# M8341X.net
KiCad netlist of a schematic drawn in EAGLE
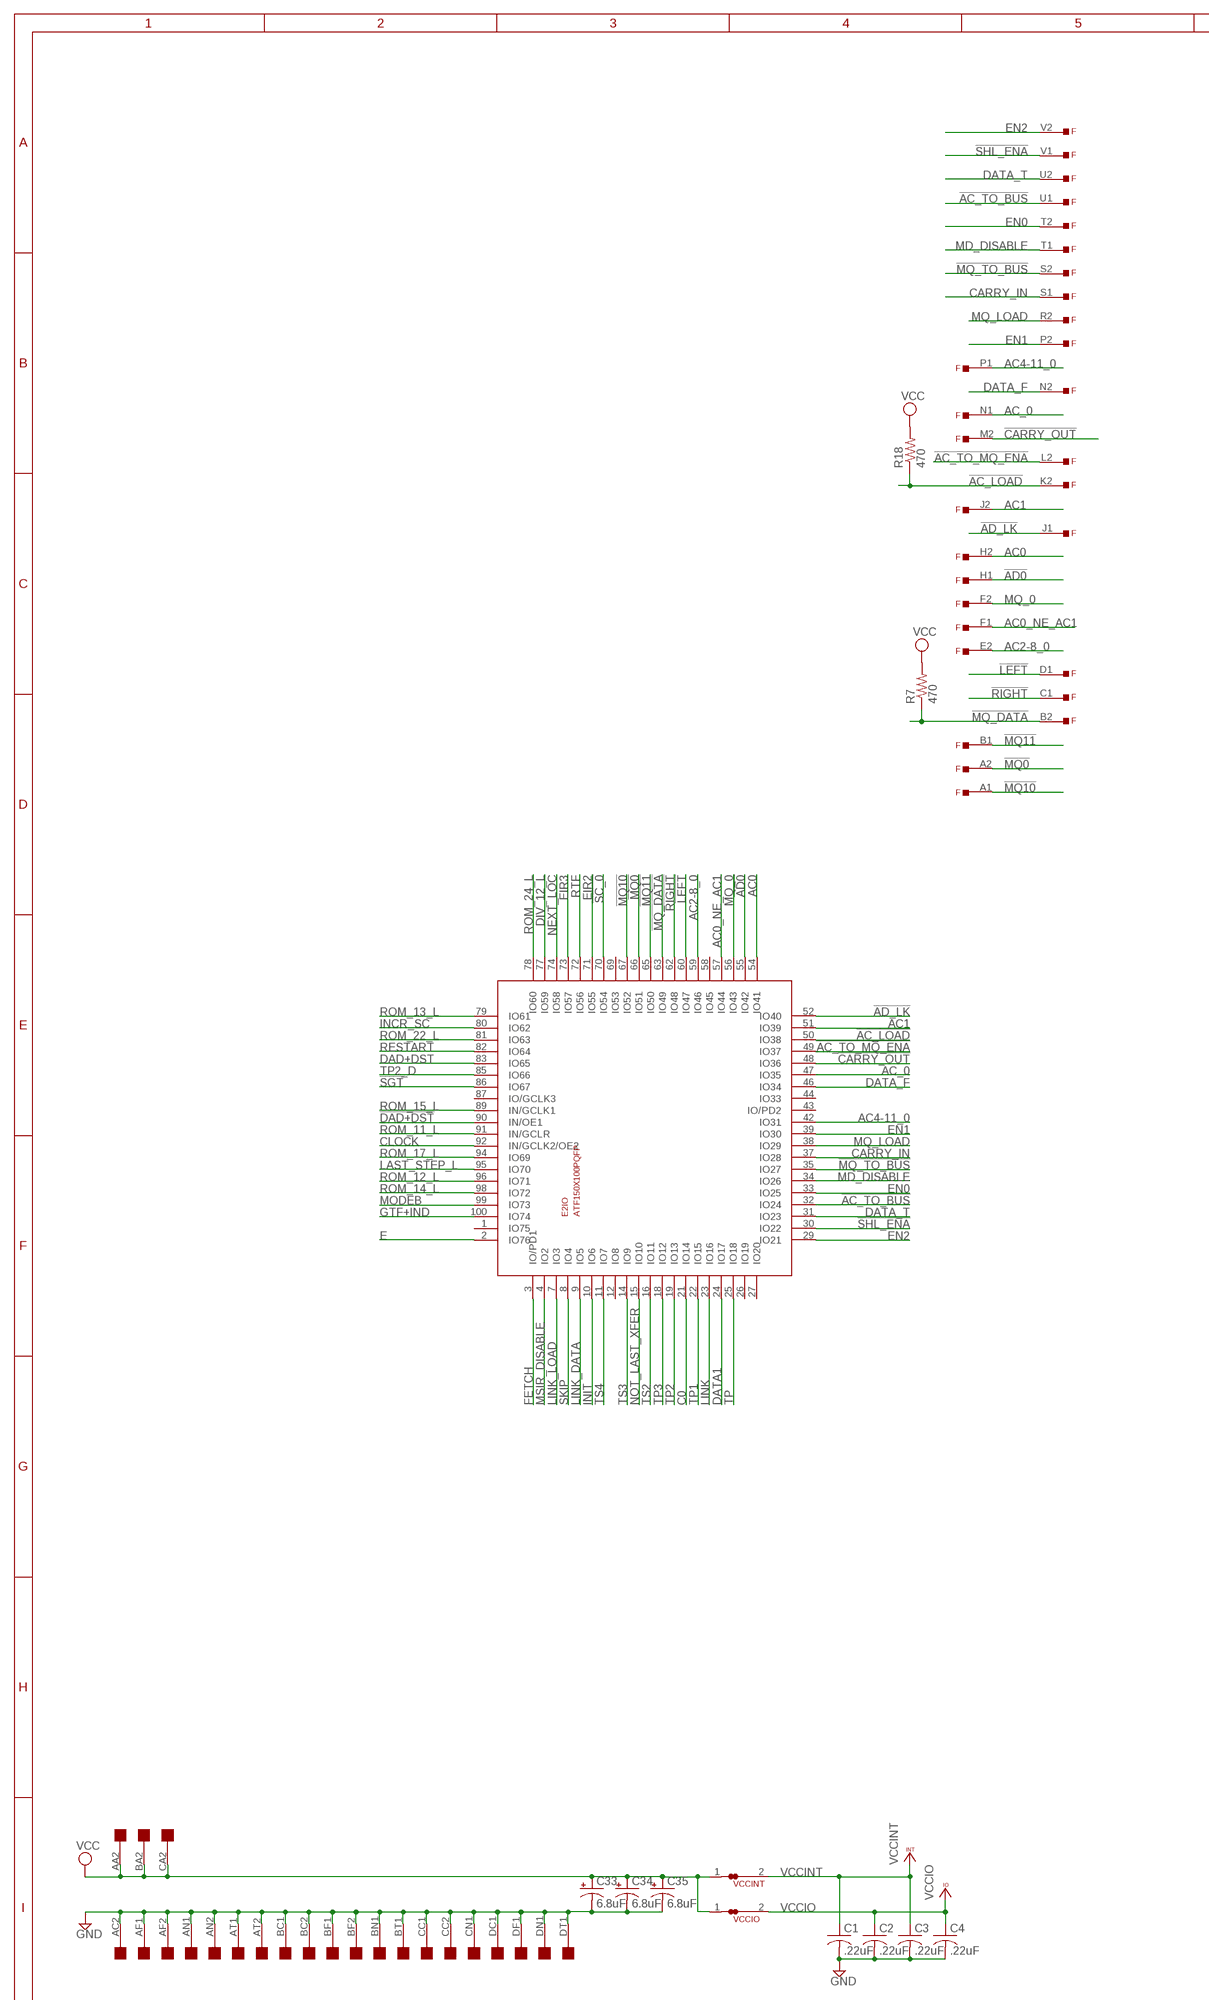
[diagram p0: schematic, sheet 1, part 1 of 2]
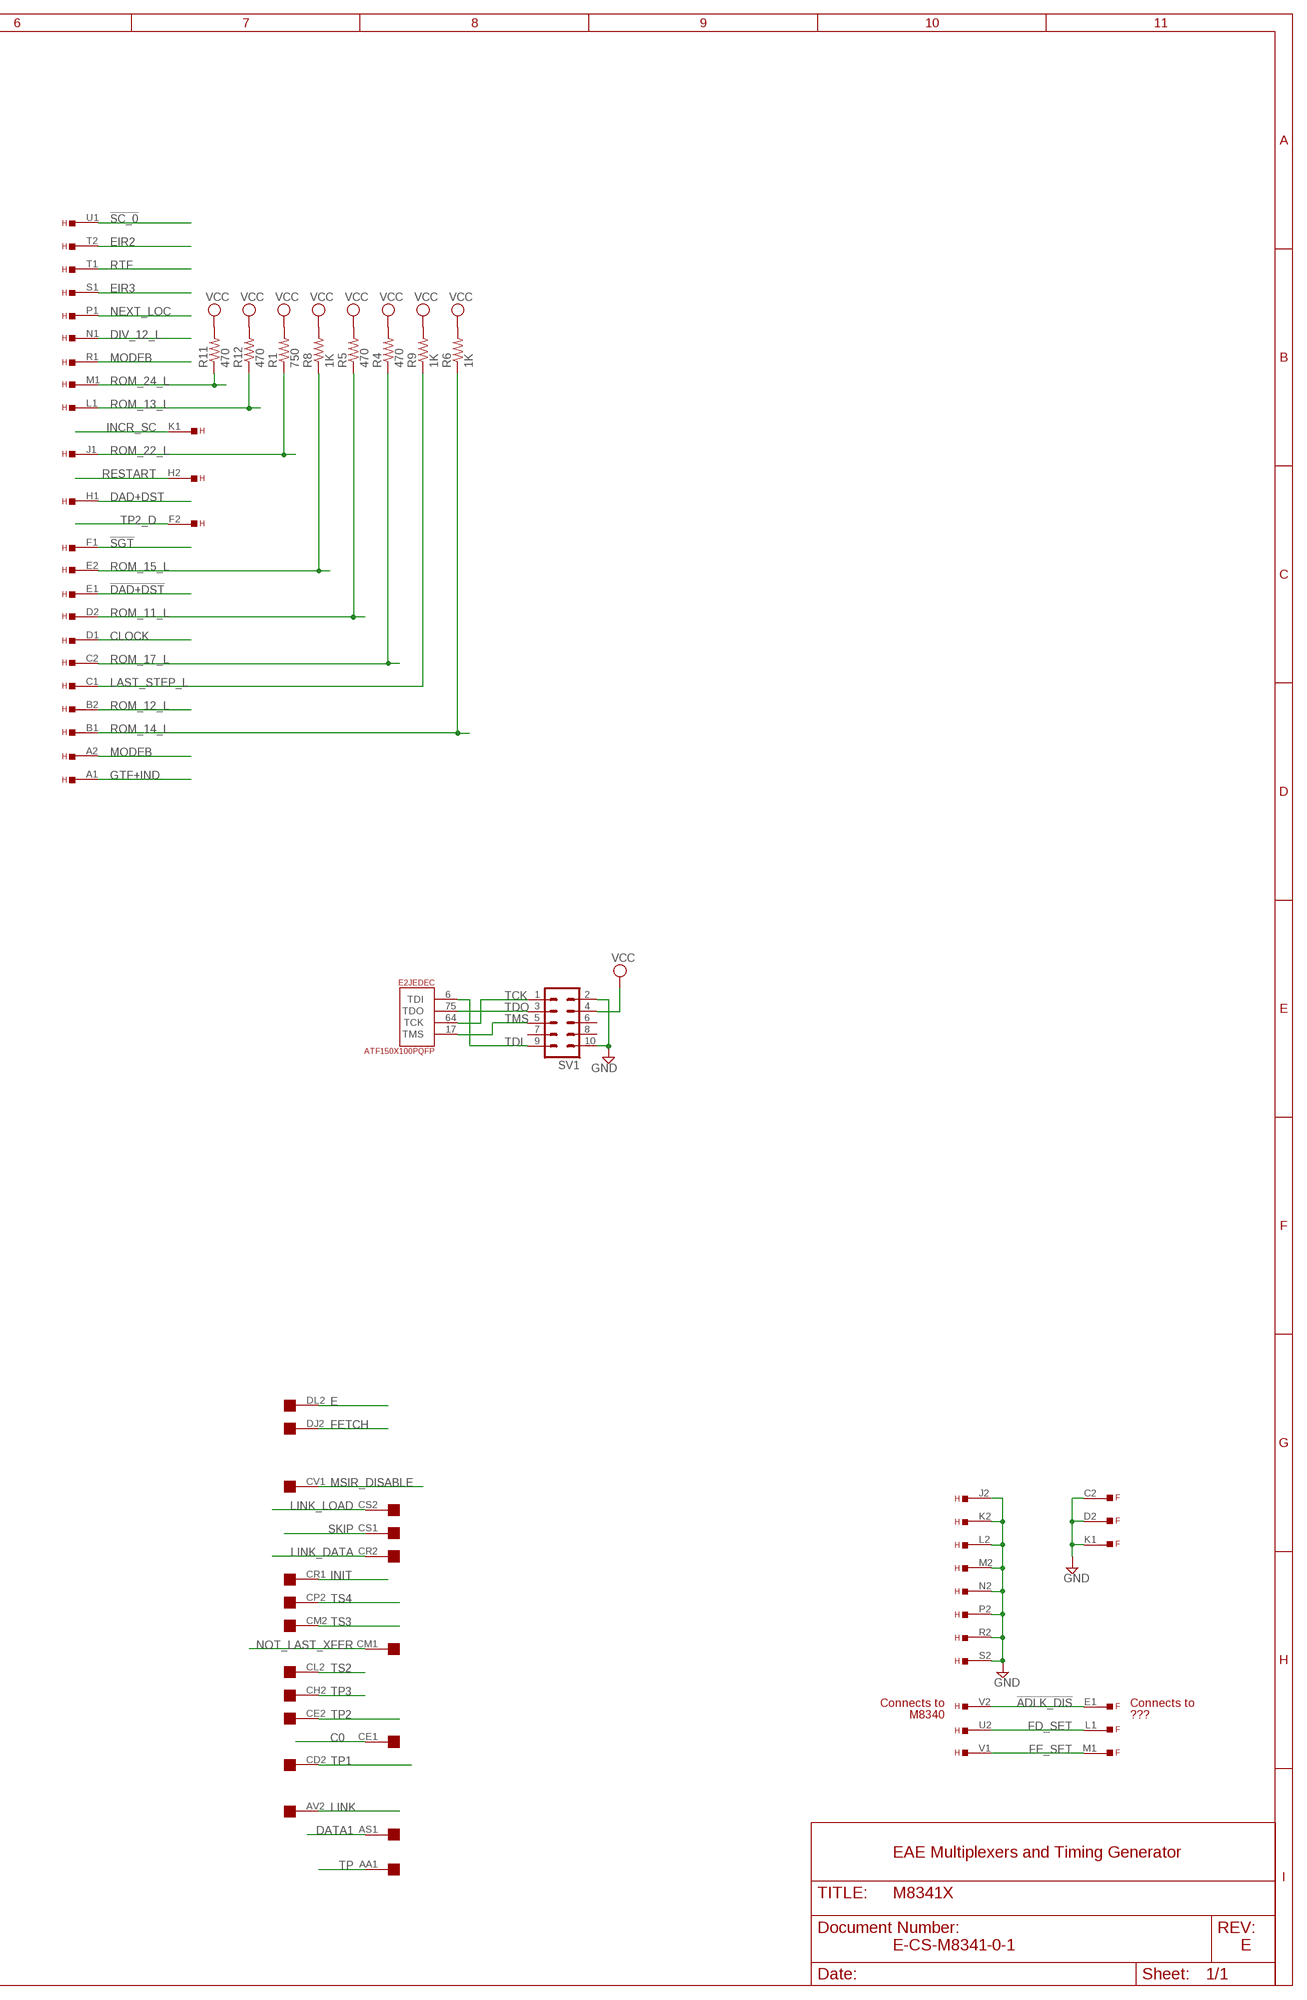
[diagram p1: schematic, sheet 1, part 2 of 2]

(export (version "E")
  (design (tool "Eeschema 10.0.6"))
  (components
    (comp (ref "C1")
      (value ".22uF")
      (footprint "eagle-import:C063-025X075")
      (libsource (lib "eagle-import") (part "C-US"))
    )
    (comp (ref "C2")
      (value ".22uF")
      (footprint "eagle-import:C063-025X075")
      (libsource (lib "eagle-import") (part "C-US"))
    )
    (comp (ref "C3")
      (value ".22uF")
      (footprint "eagle-import:C063-025X075")
      (libsource (lib "eagle-import") (part "C-US"))
    )
    (comp (ref "C4")
      (value ".22uF")
      (footprint "eagle-import:C063-025X075")
      (libsource (lib "eagle-import") (part "C-US"))
    )
    (comp (ref "C33")
      (value "6.8uF")
      (footprint "eagle-import:E12-8")
      (libsource (lib "eagle-import") (part "CPOL-USE20-8AXIAL"))
    )
    (comp (ref "C34")
      (value "6.8uF")
      (footprint "eagle-import:E12-8")
      (libsource (lib "eagle-import") (part "CPOL-USE20-8AXIAL"))
    )
    (comp (ref "C35")
      (value "6.8uF")
      (footprint "eagle-import:E12-8")
      (libsource (lib "eagle-import") (part "CPOL-USE20-8AXIAL"))
    )
    (comp (ref "E2")
      (value "ATF150X100PQFP")
      (footprint "eagle-import:PQFP-100")
      (libsource (lib "eagle-import") (part "ATF150X100PQFP"))
    )
    (comp (ref "F")
      (value "EDGE-TOP")
      (footprint "eagle-import:EDGE-CON2")
      (libsource (lib "eagle-import") (part "EDGE-TOP"))
    )
    (comp (ref "H")
      (value "EDGE-TOP")
      (footprint "eagle-import:EDGE-CON2")
      (libsource (lib "eagle-import") (part "EDGE-TOP"))
    )
    (comp (ref "R1")
      (value "750")
      (footprint "eagle-import:0207_10")
      (libsource (lib "eagle-import") (part "R-US_0207/10"))
    )
    (comp (ref "R4")
      (value "470")
      (footprint "eagle-import:0207_10")
      (libsource (lib "eagle-import") (part "R-US_0207/10"))
    )
    (comp (ref "R5")
      (value "470")
      (footprint "eagle-import:0207_10")
      (libsource (lib "eagle-import") (part "R-US_0207/10"))
    )
    (comp (ref "R6")
      (value "1K")
      (footprint "eagle-import:0207_10")
      (libsource (lib "eagle-import") (part "R-US_0207/10"))
    )
    (comp (ref "R7")
      (value "470")
      (footprint "eagle-import:0207_10")
      (libsource (lib "eagle-import") (part "R-US_0207/10"))
    )
    (comp (ref "R8")
      (value "1K")
      (footprint "eagle-import:0207_10")
      (libsource (lib "eagle-import") (part "R-US_0207/10"))
    )
    (comp (ref "R9")
      (value "1K")
      (footprint "eagle-import:0207_10")
      (libsource (lib "eagle-import") (part "R-US_0207/10"))
    )
    (comp (ref "R11")
      (value "470")
      (footprint "eagle-import:0207_10")
      (libsource (lib "eagle-import") (part "R-US_0207/10"))
    )
    (comp (ref "R12")
      (value "470")
      (footprint "eagle-import:0207_10")
      (libsource (lib "eagle-import") (part "R-US_0207/10"))
    )
    (comp (ref "R18")
      (value "470")
      (footprint "eagle-import:0207_10")
      (libsource (lib "eagle-import") (part "R-US_0207/10"))
    )
    (comp (ref "SV1")
      (value "ML10")
      (footprint "eagle-import:ML10")
      (libsource (lib "eagle-import") (part "ML10"))
    )
    (comp (ref "U$2")
      (value "QUAD")
      (footprint "eagle-import:EDGE-CON8")
      (libsource (lib "eagle-import") (part "QUAD"))
    )
    (comp (ref "VCCINT")
      (value "JUMPER-NC1")
      (footprint "eagle-import:NC1")
      (libsource (lib "eagle-import") (part "JUMPER-NC1"))
    )
    (comp (ref "VCCIO")
      (value "JUMPER-NC1")
      (footprint "eagle-import:NC1")
      (libsource (lib "eagle-import") (part "JUMPER-NC1"))
    )
  )
  (nets
    (net (code "1") (name "/AC0") (class "Default")
      (node (ref "E2") (pin "54") (pinfunction "IO41_54") (pintype "bidirectional"))
      (node (ref "F") (pin "H2") (pinfunction "P_H2") (pintype "passive"))
    )
    (net (code "2") (name "/AC0_NE_AC1") (class "Default")
      (node (ref "E2") (pin "57") (pinfunction "IO44_57") (pintype "bidirectional"))
      (node (ref "F") (pin "F1") (pinfunction "P_F1") (pintype "passive"))
    )
    (net (code "3") (name "/AC1") (class "Default")
      (node (ref "E2") (pin "51") (pinfunction "IO39_51") (pintype "bidirectional"))
      (node (ref "F") (pin "J2") (pinfunction "P_J2") (pintype "passive"))
    )
    (net (code "4") (name "/AC2-8_0") (class "Default")
      (node (ref "E2") (pin "59") (pinfunction "IO46_59") (pintype "bidirectional"))
      (node (ref "F") (pin "E2") (pinfunction "P_E2") (pintype "passive"))
    )
    (net (code "5") (name "/AC4-11_0") (class "Default")
      (node (ref "E2") (pin "42") (pinfunction "IO31_42") (pintype "bidirectional"))
      (node (ref "F") (pin "P1") (pinfunction "P_P1") (pintype "passive"))
    )
    (net (code "6") (name "/AC_0") (class "Default")
      (node (ref "E2") (pin "47") (pinfunction "IO35_47") (pintype "bidirectional"))
      (node (ref "F") (pin "N1") (pinfunction "P_N1") (pintype "passive"))
    )
    (net (code "7") (name "/C0") (class "Default")
      (node (ref "E2") (pin "21") (pinfunction "IO14_21") (pintype "bidirectional"))
      (node (ref "U$2") (pin "CE1") (pinfunction "1_CE1") (pintype "bidirectional"))
    )
    (net (code "8") (name "/CARRY_IN") (class "Default")
      (node (ref "E2") (pin "37") (pinfunction "IO28_37") (pintype "bidirectional"))
      (node (ref "F") (pin "S1") (pinfunction "P_S1") (pintype "passive"))
    )
    (net (code "9") (name "/CLOCK") (class "Default")
      (node (ref "E2") (pin "92") (pinfunction "IN/GCLK2/OE2_92") (pintype "input"))
      (node (ref "H") (pin "D1") (pinfunction "P_D1") (pintype "passive"))
    )
    (net (code "10") (name "/DAD+DST") (class "Default")
      (node (ref "E2") (pin "83") (pinfunction "IO65_83") (pintype "bidirectional"))
      (node (ref "H") (pin "H1") (pinfunction "P_H1") (pintype "passive"))
    )
    (net (code "11") (name "/DATA1") (class "Default")
      (node (ref "E2") (pin "24") (pinfunction "IO17_24") (pintype "bidirectional"))
      (node (ref "U$2") (pin "AS1") (pinfunction "1_AS1") (pintype "bidirectional"))
    )
    (net (code "12") (name "/DATA_F") (class "Default")
      (node (ref "E2") (pin "46") (pinfunction "IO34_46") (pintype "bidirectional"))
      (node (ref "F") (pin "N2") (pinfunction "P_N2") (pintype "passive"))
    )
    (net (code "13") (name "/DATA_T") (class "Default")
      (node (ref "E2") (pin "31") (pinfunction "IO23_31") (pintype "bidirectional"))
      (node (ref "F") (pin "U2") (pinfunction "P_U2") (pintype "passive"))
    )
    (net (code "14") (name "/DIV_12_L") (class "Default")
      (node (ref "E2") (pin "77") (pinfunction "IO59_77") (pintype "bidirectional"))
      (node (ref "H") (pin "N1") (pinfunction "P_N1") (pintype "passive"))
    )
    (net (code "15") (name "/E") (class "Default")
      (node (ref "E2") (pin "2") (pinfunction "IO76_2") (pintype "bidirectional"))
      (node (ref "U$2") (pin "DL2") (pinfunction "1_DL2") (pintype "bidirectional"))
    )
    (net (code "16") (name "/EIR2") (class "Default")
      (node (ref "E2") (pin "71") (pinfunction "IO55_71") (pintype "bidirectional"))
      (node (ref "H") (pin "T2") (pinfunction "P_T2") (pintype "passive"))
    )
    (net (code "17") (name "/EIR3") (class "Default")
      (node (ref "E2") (pin "73") (pinfunction "IO57_73") (pintype "bidirectional"))
      (node (ref "H") (pin "S1") (pinfunction "P_S1") (pintype "passive"))
    )
    (net (code "18") (name "/EN0") (class "Default")
      (node (ref "E2") (pin "33") (pinfunction "IO25_33") (pintype "bidirectional"))
      (node (ref "F") (pin "T2") (pinfunction "P_T2") (pintype "passive"))
    )
    (net (code "19") (name "/EN1") (class "Default")
      (node (ref "E2") (pin "39") (pinfunction "IO30_39") (pintype "bidirectional"))
      (node (ref "F") (pin "P2") (pinfunction "P_P2") (pintype "passive"))
    )
    (net (code "20") (name "/EN2") (class "Default")
      (node (ref "E2") (pin "29") (pinfunction "IO21_29") (pintype "bidirectional"))
      (node (ref "F") (pin "V2") (pinfunction "P_V2") (pintype "passive"))
    )
    (net (code "21") (name "/FD_SET") (class "Default")
      (node (ref "F") (pin "L1") (pinfunction "P_L1") (pintype "passive"))
      (node (ref "H") (pin "U2") (pinfunction "P_U2") (pintype "passive"))
    )
    (net (code "22") (name "/FETCH") (class "Default")
      (node (ref "E2") (pin "3") (pinfunction "IO/PD1_3") (pintype "bidirectional"))
      (node (ref "U$2") (pin "DJ2") (pinfunction "1_DJ2") (pintype "bidirectional"))
    )
    (net (code "23") (name "/FE_SET") (class "Default")
      (node (ref "F") (pin "M1") (pinfunction "P_M1") (pintype "passive"))
      (node (ref "H") (pin "V1") (pinfunction "P_V1") (pintype "passive"))
    )
    (net (code "24") (name "/GTF+IND") (class "Default")
      (node (ref "E2") (pin "100") (pinfunction "IO74_100") (pintype "bidirectional"))
      (node (ref "H") (pin "A1") (pinfunction "P_A1") (pintype "passive"))
    )
    (net (code "25") (name "/INCR_SC") (class "Default")
      (node (ref "E2") (pin "80") (pinfunction "IO62_80") (pintype "bidirectional"))
      (node (ref "H") (pin "K1") (pinfunction "P_K1") (pintype "passive"))
    )
    (net (code "26") (name "/INIT") (class "Default")
      (node (ref "E2") (pin "10") (pinfunction "IO6_10") (pintype "bidirectional"))
      (node (ref "U$2") (pin "CR1") (pinfunction "1_CR1") (pintype "bidirectional"))
    )
    (net (code "27") (name "/LAST_STEP_L") (class "Default")
      (node (ref "E2") (pin "95") (pinfunction "IO70_95") (pintype "bidirectional"))
      (node (ref "H") (pin "C1") (pinfunction "P_C1") (pintype "passive"))
      (node (ref "R9") (pin "1") (pinfunction "1_1") (pintype "passive"))
    )
    (net (code "28") (name "/LINK") (class "Default")
      (node (ref "E2") (pin "23") (pinfunction "IO16_23") (pintype "bidirectional"))
      (node (ref "U$2") (pin "AV2") (pinfunction "1_AV2") (pintype "bidirectional"))
    )
    (net (code "29") (name "/LINK_DATA") (class "Default")
      (node (ref "E2") (pin "9") (pinfunction "IO5_9") (pintype "bidirectional"))
      (node (ref "U$2") (pin "CR2") (pinfunction "1_CR2") (pintype "bidirectional"))
    )
    (net (code "30") (name "/LINK_LOAD") (class "Default")
      (node (ref "E2") (pin "7") (pinfunction "IO3_7") (pintype "bidirectional"))
      (node (ref "U$2") (pin "CS2") (pinfunction "1_CS2") (pintype "bidirectional"))
    )
    (net (code "31") (name "/MD_DISABLE") (class "Default")
      (node (ref "E2") (pin "34") (pinfunction "IO26_34") (pintype "bidirectional"))
      (node (ref "F") (pin "T1") (pinfunction "P_T1") (pintype "passive"))
    )
    (net (code "32") (name "/MODEB") (class "Default")
      (node (ref "E2") (pin "99") (pinfunction "IO73_99") (pintype "bidirectional"))
      (node (ref "H") (pin "A2") (pinfunction "P_A2") (pintype "passive"))
      (node (ref "H") (pin "R1") (pinfunction "P_R1") (pintype "passive"))
    )
    (net (code "33") (name "/MQ_0") (class "Default")
      (node (ref "E2") (pin "56") (pinfunction "IO43_56") (pintype "bidirectional"))
      (node (ref "F") (pin "F2") (pinfunction "P_F2") (pintype "passive"))
    )
    (net (code "34") (name "/MQ_LOAD") (class "Default")
      (node (ref "E2") (pin "38") (pinfunction "IO29_38") (pintype "bidirectional"))
      (node (ref "F") (pin "R2") (pinfunction "P_R2") (pintype "passive"))
    )
    (net (code "35") (name "/MSIR_DISABLE") (class "Default")
      (node (ref "E2") (pin "4") (pinfunction "IO2_4") (pintype "bidirectional"))
      (node (ref "U$2") (pin "CV1") (pinfunction "1_CV1") (pintype "bidirectional"))
    )
    (net (code "36") (name "/NEXT_LOC") (class "Default")
      (node (ref "E2") (pin "74") (pinfunction "IO58_74") (pintype "bidirectional"))
      (node (ref "H") (pin "P1") (pinfunction "P_P1") (pintype "passive"))
    )
    (net (code "37") (name "/NOT_LAST_XFER") (class "Default")
      (node (ref "E2") (pin "15") (pinfunction "IO10_15") (pintype "bidirectional"))
      (node (ref "U$2") (pin "CM1") (pinfunction "1_CM1") (pintype "bidirectional"))
    )
    (net (code "38") (name "/RESTART") (class "Default")
      (node (ref "E2") (pin "82") (pinfunction "IO64_82") (pintype "bidirectional"))
      (node (ref "H") (pin "H2") (pinfunction "P_H2") (pintype "passive"))
    )
    (net (code "39") (name "/ROM_11_L") (class "Default")
      (node (ref "E2") (pin "91") (pinfunction "IN/GCLR_91") (pintype "input"))
      (node (ref "H") (pin "D2") (pinfunction "P_D2") (pintype "passive"))
      (node (ref "R5") (pin "1") (pinfunction "1_1") (pintype "passive"))
    )
    (net (code "40") (name "/ROM_12_L") (class "Default")
      (node (ref "E2") (pin "96") (pinfunction "IO71_96") (pintype "bidirectional"))
      (node (ref "H") (pin "B2") (pinfunction "P_B2") (pintype "passive"))
    )
    (net (code "41") (name "/ROM_13_L") (class "Default")
      (node (ref "E2") (pin "79") (pinfunction "IO61_79") (pintype "bidirectional"))
      (node (ref "H") (pin "L1") (pinfunction "P_L1") (pintype "passive"))
      (node (ref "R12") (pin "1") (pinfunction "1_1") (pintype "passive"))
    )
    (net (code "42") (name "/ROM_14_L") (class "Default")
      (node (ref "E2") (pin "98") (pinfunction "IO72_98") (pintype "bidirectional"))
      (node (ref "H") (pin "B1") (pinfunction "P_B1") (pintype "passive"))
      (node (ref "R6") (pin "1") (pinfunction "1_1") (pintype "passive"))
    )
    (net (code "43") (name "/ROM_15_L") (class "Default")
      (node (ref "E2") (pin "89") (pinfunction "IN/GCLK1_89") (pintype "input"))
      (node (ref "H") (pin "E2") (pinfunction "P_E2") (pintype "passive"))
      (node (ref "R8") (pin "1") (pinfunction "1_1") (pintype "passive"))
    )
    (net (code "44") (name "/ROM_17_L") (class "Default")
      (node (ref "E2") (pin "94") (pinfunction "IO69_94") (pintype "bidirectional"))
      (node (ref "H") (pin "C2") (pinfunction "P_C2") (pintype "passive"))
      (node (ref "R4") (pin "1") (pinfunction "1_1") (pintype "passive"))
    )
    (net (code "45") (name "/ROM_22_L") (class "Default")
      (node (ref "E2") (pin "81") (pinfunction "IO63_81") (pintype "bidirectional"))
      (node (ref "H") (pin "J1") (pinfunction "P_J1") (pintype "passive"))
      (node (ref "R1") (pin "1") (pinfunction "1_1") (pintype "passive"))
    )
    (net (code "46") (name "/ROM_24_L") (class "Default")
      (node (ref "E2") (pin "78") (pinfunction "IO60_78") (pintype "bidirectional"))
      (node (ref "H") (pin "M1") (pinfunction "P_M1") (pintype "passive"))
      (node (ref "R11") (pin "1") (pinfunction "1_1") (pintype "passive"))
    )
    (net (code "47") (name "/RTF") (class "Default")
      (node (ref "E2") (pin "72") (pinfunction "IO56_72") (pintype "bidirectional"))
      (node (ref "H") (pin "T1") (pinfunction "P_T1") (pintype "passive"))
    )
    (net (code "48") (name "/SKIP") (class "Default")
      (node (ref "E2") (pin "8") (pinfunction "IO4_8") (pintype "bidirectional"))
      (node (ref "U$2") (pin "CS1") (pinfunction "1_CS1") (pintype "bidirectional"))
    )
    (net (code "49") (name "/TCK") (class "Default")
      (node (ref "E2") (pin "64") (pinfunction "TCK_64") (pintype "bidirectional"))
      (node (ref "SV1") (pin "1") (pinfunction "1_1") (pintype "passive"))
    )
    (net (code "50") (name "/TDI") (class "Default")
      (node (ref "E2") (pin "6") (pinfunction "TDI_6") (pintype "bidirectional"))
      (node (ref "SV1") (pin "9") (pinfunction "9_9") (pintype "passive"))
    )
    (net (code "51") (name "/TDO") (class "Default")
      (node (ref "E2") (pin "75") (pinfunction "TDO_75") (pintype "bidirectional"))
      (node (ref "SV1") (pin "3") (pinfunction "3_3") (pintype "passive"))
    )
    (net (code "52") (name "/TMS") (class "Default")
      (node (ref "E2") (pin "17") (pinfunction "TMS_17") (pintype "bidirectional"))
      (node (ref "SV1") (pin "5") (pinfunction "5_5") (pintype "passive"))
    )
    (net (code "53") (name "/TP") (class "Default")
      (node (ref "E2") (pin "25") (pinfunction "IO18_25") (pintype "bidirectional"))
      (node (ref "U$2") (pin "AA1") (pinfunction "1_AA1") (pintype "bidirectional"))
    )
    (net (code "54") (name "/TP1") (class "Default")
      (node (ref "E2") (pin "22") (pinfunction "IO15_22") (pintype "bidirectional"))
      (node (ref "U$2") (pin "CD2") (pinfunction "1_CD2") (pintype "bidirectional"))
    )
    (net (code "55") (name "/TP2") (class "Default")
      (node (ref "E2") (pin "19") (pinfunction "IO13_19") (pintype "bidirectional"))
      (node (ref "U$2") (pin "CE2") (pinfunction "1_CE2") (pintype "bidirectional"))
    )
    (net (code "56") (name "/TP2_D") (class "Default")
      (node (ref "E2") (pin "85") (pinfunction "IO66_85") (pintype "bidirectional"))
      (node (ref "H") (pin "F2") (pinfunction "P_F2") (pintype "passive"))
    )
    (net (code "57") (name "/TP3") (class "Default")
      (node (ref "E2") (pin "18") (pinfunction "IO12_18") (pintype "bidirectional"))
      (node (ref "U$2") (pin "CH2") (pinfunction "1_CH2") (pintype "bidirectional"))
    )
    (net (code "58") (name "/TS2") (class "Default")
      (node (ref "E2") (pin "16") (pinfunction "IO11_16") (pintype "bidirectional"))
      (node (ref "U$2") (pin "CL2") (pinfunction "1_CL2") (pintype "bidirectional"))
    )
    (net (code "59") (name "/TS3") (class "Default")
      (node (ref "E2") (pin "14") (pinfunction "IO9_14") (pintype "bidirectional"))
      (node (ref "U$2") (pin "CM2") (pinfunction "1_CM2") (pintype "bidirectional"))
    )
    (net (code "60") (name "/TS4") (class "Default")
      (node (ref "E2") (pin "11") (pinfunction "IO7_11") (pintype "bidirectional"))
      (node (ref "U$2") (pin "CP2") (pinfunction "1_CP2") (pintype "bidirectional"))
    )
    (net (code "61") (name "/~{AC_LOAD}") (class "Default")
      (node (ref "E2") (pin "50") (pinfunction "IO38_50") (pintype "bidirectional"))
      (node (ref "F") (pin "K2") (pinfunction "P_K2") (pintype "passive"))
      (node (ref "R18") (pin "1") (pinfunction "1_1") (pintype "passive"))
    )
    (net (code "62") (name "/~{AC_TO_BUS}") (class "Default")
      (node (ref "E2") (pin "32") (pinfunction "IO24_32") (pintype "bidirectional"))
      (node (ref "F") (pin "U1") (pinfunction "P_U1") (pintype "passive"))
    )
    (net (code "63") (name "/~{AC_TO_MQ_ENA}") (class "Default")
      (node (ref "E2") (pin "49") (pinfunction "IO37_49") (pintype "bidirectional"))
      (node (ref "F") (pin "L2") (pinfunction "P_L2") (pintype "passive"))
    )
    (net (code "64") (name "/~{AD0}") (class "Default")
      (node (ref "E2") (pin "55") (pinfunction "IO42_55") (pintype "bidirectional"))
      (node (ref "F") (pin "H1") (pinfunction "P_H1") (pintype "passive"))
    )
    (net (code "65") (name "/~{ADLK_DIS}") (class "Default")
      (node (ref "F") (pin "E1") (pinfunction "P_E1") (pintype "passive"))
      (node (ref "H") (pin "V2") (pinfunction "P_V2") (pintype "passive"))
    )
    (net (code "66") (name "/~{AD_LK}") (class "Default")
      (node (ref "E2") (pin "52") (pinfunction "IO40_52") (pintype "bidirectional"))
      (node (ref "F") (pin "J1") (pinfunction "P_J1") (pintype "passive"))
    )
    (net (code "67") (name "/~{CARRY_OUT}") (class "Default")
      (node (ref "E2") (pin "48") (pinfunction "IO36_48") (pintype "bidirectional"))
      (node (ref "F") (pin "M2") (pinfunction "P_M2") (pintype "passive"))
    )
    (net (code "68") (name "/~{DAD+DST}") (class "Default")
      (node (ref "E2") (pin "90") (pinfunction "IN/OE1_90") (pintype "input"))
      (node (ref "H") (pin "E1") (pinfunction "P_E1") (pintype "passive"))
    )
    (net (code "69") (name "/~{LEFT}") (class "Default")
      (node (ref "E2") (pin "60") (pinfunction "IO47_60") (pintype "bidirectional"))
      (node (ref "F") (pin "D1") (pinfunction "P_D1") (pintype "passive"))
    )
    (net (code "70") (name "/~{MQ0}") (class "Default")
      (node (ref "E2") (pin "66") (pinfunction "IO51_66") (pintype "bidirectional"))
      (node (ref "F") (pin "A2") (pinfunction "P_A2") (pintype "passive"))
    )
    (net (code "71") (name "/~{MQ10}") (class "Default")
      (node (ref "E2") (pin "67") (pinfunction "IO52_67") (pintype "bidirectional"))
      (node (ref "F") (pin "A1") (pinfunction "P_A1") (pintype "passive"))
    )
    (net (code "72") (name "/~{MQ11}") (class "Default")
      (node (ref "E2") (pin "65") (pinfunction "IO50_65") (pintype "bidirectional"))
      (node (ref "F") (pin "B1") (pinfunction "P_B1") (pintype "passive"))
    )
    (net (code "73") (name "/~{MQ_DATA}") (class "Default")
      (node (ref "E2") (pin "63") (pinfunction "IO49_63") (pintype "bidirectional"))
      (node (ref "F") (pin "B2") (pinfunction "P_B2") (pintype "passive"))
      (node (ref "R7") (pin "1") (pinfunction "1_1") (pintype "passive"))
    )
    (net (code "74") (name "/~{MQ_TO_BUS}") (class "Default")
      (node (ref "E2") (pin "35") (pinfunction "IO27_35") (pintype "bidirectional"))
      (node (ref "F") (pin "S2") (pinfunction "P_S2") (pintype "passive"))
    )
    (net (code "75") (name "/~{RIGHT}") (class "Default")
      (node (ref "E2") (pin "62") (pinfunction "IO48_62") (pintype "bidirectional"))
      (node (ref "F") (pin "C1") (pinfunction "P_C1") (pintype "passive"))
    )
    (net (code "76") (name "/~{SC_0}") (class "Default")
      (node (ref "E2") (pin "70") (pinfunction "IO54_70") (pintype "bidirectional"))
      (node (ref "H") (pin "U1") (pinfunction "P_U1") (pintype "passive"))
    )
    (net (code "77") (name "/~{SGT}") (class "Default")
      (node (ref "E2") (pin "86") (pinfunction "IO67_86") (pintype "bidirectional"))
      (node (ref "H") (pin "F1") (pinfunction "P_F1") (pintype "passive"))
    )
    (net (code "78") (name "/~{SHL_ENA}") (class "Default")
      (node (ref "E2") (pin "30") (pinfunction "IO22_30") (pintype "bidirectional"))
      (node (ref "F") (pin "V1") (pinfunction "P_V1") (pintype "passive"))
    )
    (net (code "79") (name "GND") (class "Default")
      (node (ref "C1") (pin "2") (pinfunction "2_2") (pintype "passive"))
      (node (ref "C2") (pin "2") (pinfunction "2_2") (pintype "passive"))
      (node (ref "C3") (pin "2") (pinfunction "2_2") (pintype "passive"))
      (node (ref "C33") (pin "-") (pinfunction "-_-") (pintype "passive"))
      (node (ref "C34") (pin "-") (pinfunction "-_-") (pintype "passive"))
      (node (ref "C35") (pin "-") (pinfunction "-_-") (pintype "passive"))
      (node (ref "C4") (pin "2") (pinfunction "2_2") (pintype "passive"))
      (node (ref "F") (pin "C2") (pinfunction "P_C2") (pintype "passive"))
      (node (ref "F") (pin "D2") (pinfunction "P_D2") (pintype "passive"))
      (node (ref "F") (pin "K1") (pinfunction "P_K1") (pintype "passive"))
      (node (ref "H") (pin "J2") (pinfunction "P_J2") (pintype "passive"))
      (node (ref "H") (pin "K2") (pinfunction "P_K2") (pintype "passive"))
      (node (ref "H") (pin "L2") (pinfunction "P_L2") (pintype "passive"))
      (node (ref "H") (pin "M2") (pinfunction "P_M2") (pintype "passive"))
      (node (ref "H") (pin "N2") (pinfunction "P_N2") (pintype "passive"))
      (node (ref "H") (pin "P2") (pinfunction "P_P2") (pintype "passive"))
      (node (ref "H") (pin "R2") (pinfunction "P_R2") (pintype "passive"))
      (node (ref "H") (pin "S2") (pinfunction "P_S2") (pintype "passive"))
      (node (ref "SV1") (pin "10") (pinfunction "10_10") (pintype "passive"))
      (node (ref "SV1") (pin "2") (pinfunction "2_2") (pintype "passive"))
      (node (ref "U$2") (pin "AC2") (pinfunction "1_AC2") (pintype "bidirectional"))
      (node (ref "U$2") (pin "AF1") (pinfunction "1_AF1") (pintype "bidirectional"))
      (node (ref "U$2") (pin "AF2") (pinfunction "1_AF2") (pintype "bidirectional"))
      (node (ref "U$2") (pin "AN1") (pinfunction "1_AN1") (pintype "bidirectional"))
      (node (ref "U$2") (pin "AN2") (pinfunction "1_AN2") (pintype "bidirectional"))
      (node (ref "U$2") (pin "AT1") (pinfunction "1_AT1") (pintype "bidirectional"))
      (node (ref "U$2") (pin "AT2") (pinfunction "1_AT2") (pintype "bidirectional"))
      (node (ref "U$2") (pin "BC1") (pinfunction "1_BC1") (pintype "bidirectional"))
      (node (ref "U$2") (pin "BC2") (pinfunction "1_BC2") (pintype "bidirectional"))
      (node (ref "U$2") (pin "BF1") (pinfunction "1_BF1") (pintype "bidirectional"))
      (node (ref "U$2") (pin "BF2") (pinfunction "1_BF2") (pintype "bidirectional"))
      (node (ref "U$2") (pin "BN1") (pinfunction "1_BN1") (pintype "bidirectional"))
      (node (ref "U$2") (pin "BT1") (pinfunction "1_BT1") (pintype "bidirectional"))
      (node (ref "U$2") (pin "CC1") (pinfunction "1_CC1") (pintype "bidirectional"))
      (node (ref "U$2") (pin "CC2") (pinfunction "1_CC2") (pintype "bidirectional"))
      (node (ref "U$2") (pin "CN1") (pinfunction "1_CN1") (pintype "bidirectional"))
      (node (ref "U$2") (pin "DC1") (pinfunction "1_DC1") (pintype "bidirectional"))
      (node (ref "U$2") (pin "DF1") (pinfunction "1_DF1") (pintype "bidirectional"))
      (node (ref "U$2") (pin "DN1") (pinfunction "1_DN1") (pintype "bidirectional"))
      (node (ref "U$2") (pin "DT1") (pinfunction "1_DT1") (pintype "bidirectional"))
    )
    (net (code "80") (name "VCC") (class "Default")
      (node (ref "C33") (pin "+") (pinfunction "+_+") (pintype "passive"))
      (node (ref "C34") (pin "+") (pinfunction "+_+") (pintype "passive"))
      (node (ref "C35") (pin "+") (pinfunction "+_+") (pintype "passive"))
      (node (ref "R1") (pin "2") (pinfunction "2_2") (pintype "passive"))
      (node (ref "R11") (pin "2") (pinfunction "2_2") (pintype "passive"))
      (node (ref "R12") (pin "2") (pinfunction "2_2") (pintype "passive"))
      (node (ref "R18") (pin "2") (pinfunction "2_2") (pintype "passive"))
      (node (ref "R4") (pin "2") (pinfunction "2_2") (pintype "passive"))
      (node (ref "R5") (pin "2") (pinfunction "2_2") (pintype "passive"))
      (node (ref "R6") (pin "2") (pinfunction "2_2") (pintype "passive"))
      (node (ref "R7") (pin "2") (pinfunction "2_2") (pintype "passive"))
      (node (ref "R8") (pin "2") (pinfunction "2_2") (pintype "passive"))
      (node (ref "R9") (pin "2") (pinfunction "2_2") (pintype "passive"))
      (node (ref "SV1") (pin "4") (pinfunction "4_4") (pintype "passive"))
      (node (ref "U$2") (pin "AA2") (pinfunction "1_AA2") (pintype "bidirectional"))
      (node (ref "U$2") (pin "BA2") (pinfunction "1_BA2") (pintype "bidirectional"))
      (node (ref "U$2") (pin "CA2") (pinfunction "1_CA2") (pintype "bidirectional"))
      (node (ref "VCCINT") (pin "1") (pinfunction "1_1") (pintype "bidirectional"))
      (node (ref "VCCIO") (pin "1") (pinfunction "1_1") (pintype "bidirectional"))
    )
    (net (code "81") (name "VCCINT") (class "Default")
      (node (ref "C1") (pin "1") (pinfunction "1_1") (pintype "passive"))
      (node (ref "C3") (pin "1") (pinfunction "1_1") (pintype "passive"))
      (node (ref "VCCINT") (pin "2") (pinfunction "2_2") (pintype "bidirectional"))
    )
    (net (code "82") (name "VCCIO") (class "Default")
      (node (ref "C2") (pin "1") (pinfunction "1_1") (pintype "passive"))
      (node (ref "C4") (pin "1") (pinfunction "1_1") (pintype "passive"))
      (node (ref "VCCIO") (pin "2") (pinfunction "2_2") (pintype "bidirectional"))
    )
    (net (code "83") (name "unconnected-(E2Q-IO8-Pad12)") (class "Default")
      (node (ref "E2") (pin "12") (pinfunction "IO8_12") (pintype "bidirectional"))
    )
    (net (code "84") (name "unconnected-(E2Q-IO19-Pad26)") (class "Default")
      (node (ref "E2") (pin "26") (pinfunction "IO19_26") (pintype "bidirectional"))
    )
    (net (code "85") (name "unconnected-(E2Q-IO20-Pad27)") (class "Default")
      (node (ref "E2") (pin "27") (pinfunction "IO20_27") (pintype "bidirectional"))
    )
    (net (code "86") (name "unconnected-(E2Q-IO33-Pad44)") (class "Default")
      (node (ref "E2") (pin "44") (pinfunction "IO33_44") (pintype "bidirectional"))
    )
    (net (code "87") (name "unconnected-(E2Q-IO45-Pad58)") (class "Default")
      (node (ref "E2") (pin "58") (pinfunction "IO45_58") (pintype "bidirectional"))
    )
    (net (code "88") (name "unconnected-(E2Q-IO53-Pad69)") (class "Default")
      (node (ref "E2") (pin "69") (pinfunction "IO53_69") (pintype "bidirectional"))
    )
    (net (code "89") (name "unconnected-(E2Q-IO75-Pad1)") (class "Default")
      (node (ref "E2") (pin "1") (pinfunction "IO75_1") (pintype "bidirectional"))
    )
    (net (code "90") (name "unconnected-(E2Q-IO{slash}GCLK3-Pad87)") (class "Default")
      (node (ref "E2") (pin "87") (pinfunction "IO/GCLK3_87") (pintype "bidirectional"))
    )
    (net (code "91") (name "unconnected-(E2Q-IO{slash}PD2-Pad43)") (class "Default")
      (node (ref "E2") (pin "43") (pinfunction "IO/PD2_43") (pintype "bidirectional"))
    )
    (net (code "92") (name "unconnected-(SV1-Pad6)") (class "Default")
      (node (ref "SV1") (pin "6") (pinfunction "6_6") (pintype "passive"))
    )
    (net (code "93") (name "unconnected-(SV1-Pad7)") (class "Default")
      (node (ref "SV1") (pin "7") (pinfunction "7_7") (pintype "passive"))
    )
    (net (code "94") (name "unconnected-(SV1-Pad8)") (class "Default")
      (node (ref "SV1") (pin "8") (pinfunction "8_8") (pintype "passive"))
    )
  )
)
